# bh_sensor_argri_alph.net
KiCad netlist of a schematic drawn in Altium Designer
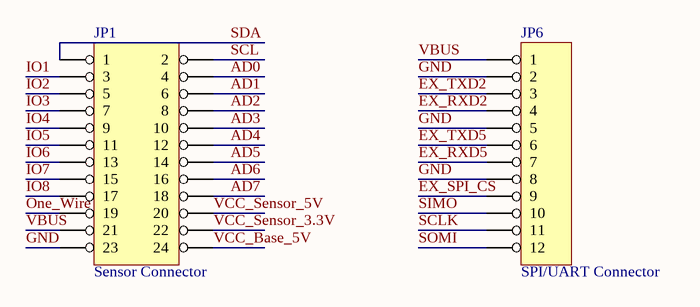
[diagram p0: bh_sensor_argri_alph.SchDoc]

(export (version "E")
  (design (tool "Eeschema 10.0.6"))
  (components
    (comp (ref "JP1")
      (value "Sensor Connector")
      (footprint "SIP2X12X2.54")
      (libsource (lib "5D_CONNECTOR") (part "SIP2X12"))
    )
    (comp (ref "JP6")
      (value "SPI/UART Connector")
      (footprint "SIP1x12x2.54")
      (description "12 Pin Header")
      (libsource (lib "5D_CONNECTOR") (part "SIP1X12"))
    )
  )
  (nets
    (net (code "1") (name "/AD0") (class "Default")
      (node (ref "JP1") (pin "4") (pinfunction "4_4") (pintype "passive"))
    )
    (net (code "2") (name "/AD1") (class "Default")
      (node (ref "JP1") (pin "6") (pinfunction "6_6") (pintype "passive"))
    )
    (net (code "3") (name "/AD2") (class "Default")
      (node (ref "JP1") (pin "8") (pinfunction "8_8") (pintype "passive"))
    )
    (net (code "4") (name "/AD3") (class "Default")
      (node (ref "JP1") (pin "10") (pinfunction "10_10") (pintype "passive"))
    )
    (net (code "5") (name "/AD4") (class "Default")
      (node (ref "JP1") (pin "12") (pinfunction "12_12") (pintype "passive"))
    )
    (net (code "6") (name "/AD5") (class "Default")
      (node (ref "JP1") (pin "14") (pinfunction "14_14") (pintype "passive"))
    )
    (net (code "7") (name "/AD6") (class "Default")
      (node (ref "JP1") (pin "16") (pinfunction "16_16") (pintype "passive"))
    )
    (net (code "8") (name "/AD7") (class "Default")
      (node (ref "JP1") (pin "18") (pinfunction "18_18") (pintype "passive"))
    )
    (net (code "9") (name "/EX_RXD2") (class "Default")
      (node (ref "JP6") (pin "4") (pinfunction "4_4") (pintype "passive"))
    )
    (net (code "10") (name "/EX_RXD5") (class "Default")
      (node (ref "JP6") (pin "7") (pinfunction "7_7") (pintype "passive"))
    )
    (net (code "11") (name "/EX_SPI_CS") (class "Default")
      (node (ref "JP6") (pin "9") (pinfunction "9_9") (pintype "passive"))
    )
    (net (code "12") (name "/EX_TXD2") (class "Default")
      (node (ref "JP6") (pin "3") (pinfunction "3_3") (pintype "passive"))
    )
    (net (code "13") (name "/EX_TXD5") (class "Default")
      (node (ref "JP6") (pin "6") (pinfunction "6_6") (pintype "passive"))
    )
    (net (code "14") (name "/GND") (class "Default")
      (node (ref "JP1") (pin "23") (pinfunction "23_23") (pintype "passive"))
      (node (ref "JP6") (pin "2") (pinfunction "2_2") (pintype "passive"))
      (node (ref "JP6") (pin "5") (pinfunction "5_5") (pintype "passive"))
      (node (ref "JP6") (pin "8") (pinfunction "8_8") (pintype "passive"))
    )
    (net (code "15") (name "/IO1") (class "Default")
      (node (ref "JP1") (pin "3") (pinfunction "3_3") (pintype "passive"))
    )
    (net (code "16") (name "/IO2") (class "Default")
      (node (ref "JP1") (pin "5") (pinfunction "5_5") (pintype "passive"))
    )
    (net (code "17") (name "/IO3") (class "Default")
      (node (ref "JP1") (pin "7") (pinfunction "7_7") (pintype "passive"))
    )
    (net (code "18") (name "/IO4") (class "Default")
      (node (ref "JP1") (pin "9") (pinfunction "9_9") (pintype "passive"))
    )
    (net (code "19") (name "/IO5") (class "Default")
      (node (ref "JP1") (pin "11") (pinfunction "11_11") (pintype "passive"))
    )
    (net (code "20") (name "/IO6") (class "Default")
      (node (ref "JP1") (pin "13") (pinfunction "13_13") (pintype "passive"))
    )
    (net (code "21") (name "/IO7") (class "Default")
      (node (ref "JP1") (pin "15") (pinfunction "15_15") (pintype "passive"))
    )
    (net (code "22") (name "/IO8") (class "Default")
      (node (ref "JP1") (pin "17") (pinfunction "17_17") (pintype "passive"))
    )
    (net (code "23") (name "/One_Wire") (class "Default")
      (node (ref "JP1") (pin "19") (pinfunction "19_19") (pintype "passive"))
    )
    (net (code "24") (name "/SCL") (class "Default")
      (node (ref "JP1") (pin "2") (pinfunction "2_2") (pintype "passive"))
    )
    (net (code "25") (name "/SCLK") (class "Default")
      (node (ref "JP6") (pin "11") (pinfunction "11_11") (pintype "passive"))
    )
    (net (code "26") (name "/SDA") (class "Default")
      (node (ref "JP1") (pin "1") (pinfunction "1_1") (pintype "passive"))
    )
    (net (code "27") (name "/SIMO") (class "Default")
      (node (ref "JP6") (pin "10") (pinfunction "10_10") (pintype "passive"))
    )
    (net (code "28") (name "/SOMI") (class "Default")
      (node (ref "JP6") (pin "12") (pinfunction "12_12") (pintype "passive"))
    )
    (net (code "29") (name "/VBUS") (class "Default")
      (node (ref "JP1") (pin "21") (pinfunction "21_21") (pintype "passive"))
      (node (ref "JP6") (pin "1") (pinfunction "1_1") (pintype "passive"))
    )
    (net (code "30") (name "/VCC_Base_5V") (class "Default")
      (node (ref "JP1") (pin "24") (pinfunction "24_24") (pintype "passive"))
    )
    (net (code "31") (name "/VCC_Sensor_3.3V") (class "Default")
      (node (ref "JP1") (pin "22") (pinfunction "22_22") (pintype "passive"))
    )
    (net (code "32") (name "/VCC_Sensor_5V") (class "Default")
      (node (ref "JP1") (pin "20") (pinfunction "20_20") (pintype "passive"))
    )
  )
)
